# EncoderPCB_V2_lower.net
KiCad netlist of a schematic drawn in EAGLE
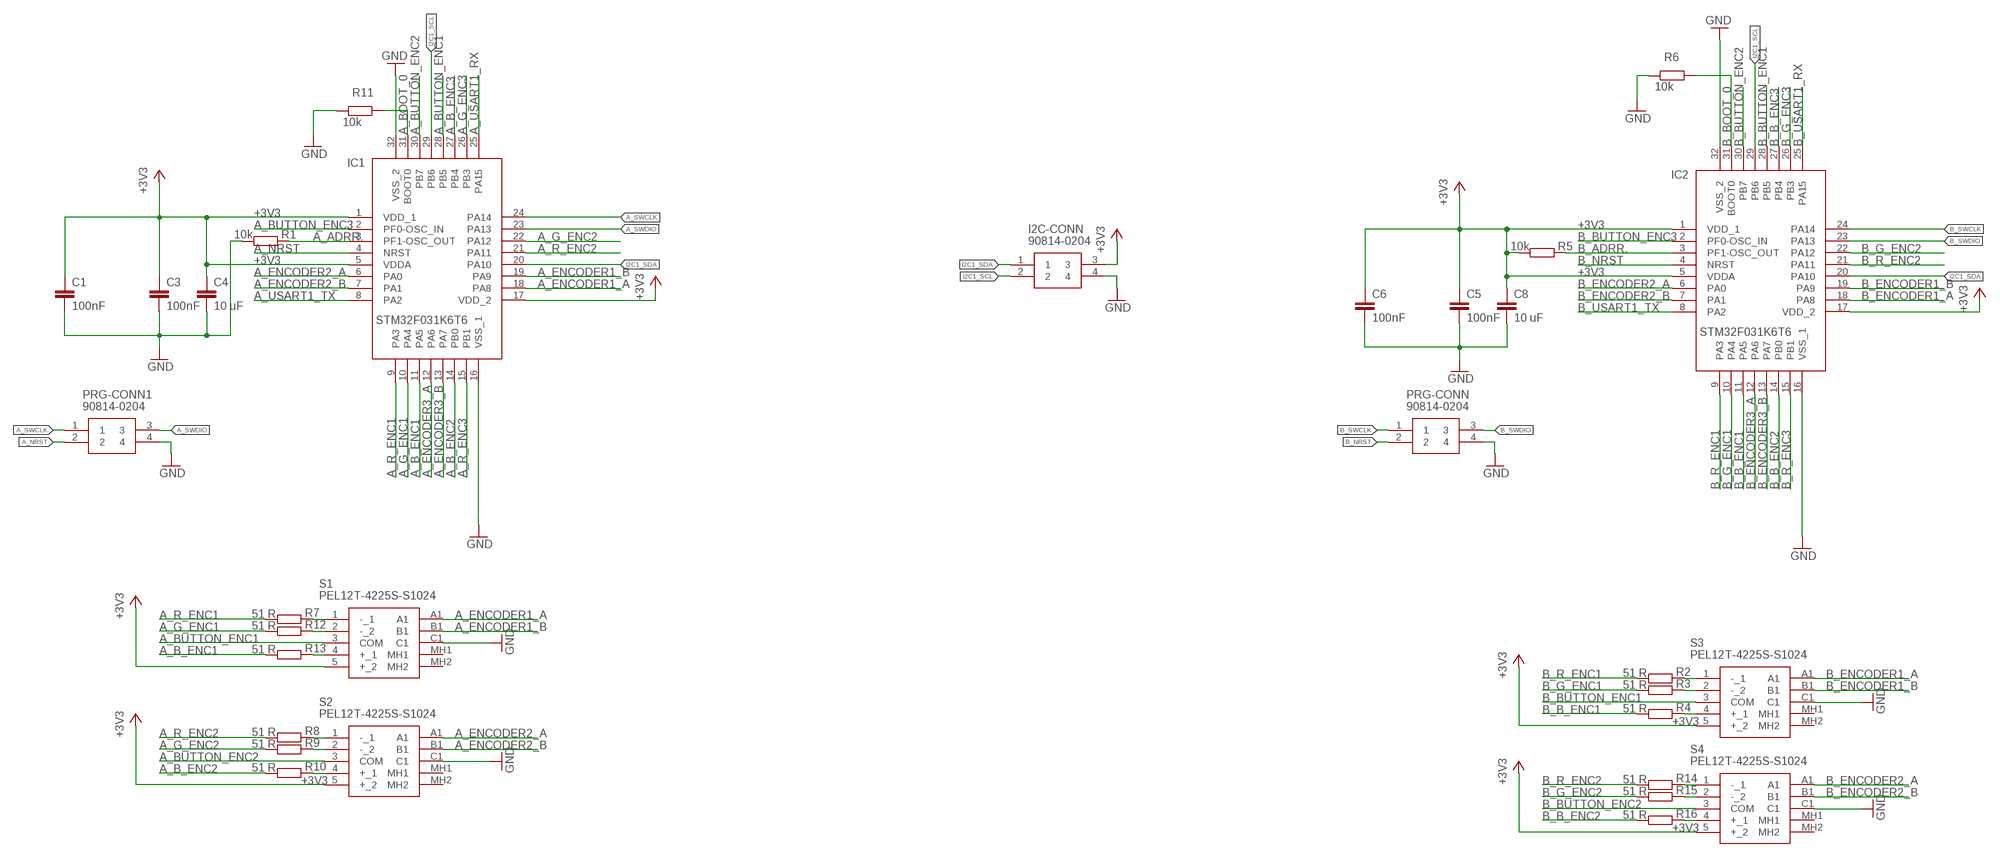
[diagram p0: schematic, sheet 1]

(export (version "E")
  (design (tool "Eeschema 10.0.6"))
  (components
    (comp (ref "C1")
      (value "100nF")
      (footprint "eagle-import:C0603")
      (libsource (lib "eagle-import") (part "CAPACITOR{dblquote}"))
    )
    (comp (ref "C3")
      (value "100nF")
      (footprint "eagle-import:C0603")
      (libsource (lib "eagle-import") (part "CAPACITOR{dblquote}"))
    )
    (comp (ref "C4")
      (value "10 uF")
      (footprint "eagle-import:C1206")
      (libsource (lib "eagle-import") (part "CAPACITOR_1206"))
    )
    (comp (ref "C5")
      (value "100nF")
      (footprint "eagle-import:C0603")
      (libsource (lib "eagle-import") (part "CAPACITOR{dblquote}"))
    )
    (comp (ref "C6")
      (value "100nF")
      (footprint "eagle-import:C0603")
      (libsource (lib "eagle-import") (part "CAPACITOR{dblquote}"))
    )
    (comp (ref "C8")
      (value "10 uF")
      (footprint "eagle-import:C1206")
      (libsource (lib "eagle-import") (part "CAPACITOR_1206"))
    )
    (comp (ref "I2C-CONN")
      (value "90814-0204")
      (footprint "eagle-import:MOLEX_90814-0204")
      (fields (field (name "MOUSER_PART_NUMBER") "538-90814-0204"))
      (libsource (lib "eagle-import") (part "90814-0204"))
    )
    (comp (ref "IC1")
      (value "STM32F031K6T6")
      (footprint "eagle-import:QFP80P900X900X160-32N")
      (fields (field (name "MOUSER_PART_NUMBER") "511-STM32F031K6T6"))
      (libsource (lib "eagle-import") (part "STM32F031K6T6"))
    )
    (comp (ref "IC2")
      (value "STM32F031K6T6")
      (footprint "eagle-import:QFP80P900X900X160-32N")
      (fields (field (name "MOUSER_PART_NUMBER") "511-STM32F031K6T6"))
      (libsource (lib "eagle-import") (part "STM32F031K6T6"))
    )
    (comp (ref "PRG-CONN")
      (value "90814-0204")
      (footprint "eagle-import:MOLEX_90814-0204")
      (fields (field (name "MOUSER_PART_NUMBER") "538-90814-0204"))
      (libsource (lib "eagle-import") (part "90814-0204"))
    )
    (comp (ref "PRG-CONN1")
      (value "90814-0204")
      (footprint "eagle-import:MOLEX_90814-0204")
      (fields (field (name "MOUSER_PART_NUMBER") "538-90814-0204"))
      (libsource (lib "eagle-import") (part "90814-0204"))
    )
    (comp (ref "R1")
      (value "10k")
      (footprint "eagle-import:R0603")
      (libsource (lib "eagle-import") (part "RESISTOR_0603"))
    )
    (comp (ref "R2")
      (value "51 R")
      (footprint "eagle-import:R0603")
      (libsource (lib "eagle-import") (part "RESISTOR_0603"))
    )
    (comp (ref "R3")
      (value "51 R")
      (footprint "eagle-import:R0603")
      (libsource (lib "eagle-import") (part "RESISTOR_0603"))
    )
    (comp (ref "R4")
      (value "51 R")
      (footprint "eagle-import:R0603")
      (libsource (lib "eagle-import") (part "RESISTOR_0603"))
    )
    (comp (ref "R5")
      (value "10k")
      (footprint "eagle-import:R0603")
      (libsource (lib "eagle-import") (part "RESISTOR_0603"))
    )
    (comp (ref "R6")
      (value "10k")
      (footprint "eagle-import:R0603")
      (libsource (lib "eagle-import") (part "RESISTOR_0603"))
    )
    (comp (ref "R7")
      (value "51 R")
      (footprint "eagle-import:R0603")
      (libsource (lib "eagle-import") (part "RESISTOR_0603"))
    )
    (comp (ref "R8")
      (value "51 R")
      (footprint "eagle-import:R0603")
      (libsource (lib "eagle-import") (part "RESISTOR_0603"))
    )
    (comp (ref "R9")
      (value "51 R")
      (footprint "eagle-import:R0603")
      (libsource (lib "eagle-import") (part "RESISTOR_0603"))
    )
    (comp (ref "R10")
      (value "51 R")
      (footprint "eagle-import:R0603")
      (libsource (lib "eagle-import") (part "RESISTOR_0603"))
    )
    (comp (ref "R11")
      (value "10k")
      (footprint "eagle-import:R0603")
      (libsource (lib "eagle-import") (part "RESISTOR_0603"))
    )
    (comp (ref "R12")
      (value "51 R")
      (footprint "eagle-import:R0603")
      (libsource (lib "eagle-import") (part "RESISTOR_0603"))
    )
    (comp (ref "R13")
      (value "51 R")
      (footprint "eagle-import:R0603")
      (libsource (lib "eagle-import") (part "RESISTOR_0603"))
    )
    (comp (ref "R14")
      (value "51 R")
      (footprint "eagle-import:R0603")
      (libsource (lib "eagle-import") (part "RESISTOR_0603"))
    )
    (comp (ref "R15")
      (value "51 R")
      (footprint "eagle-import:R0603")
      (libsource (lib "eagle-import") (part "RESISTOR_0603"))
    )
    (comp (ref "R16")
      (value "51 R")
      (footprint "eagle-import:R0603")
      (libsource (lib "eagle-import") (part "RESISTOR_0603"))
    )
    (comp (ref "S1")
      (value "PEL12T-4225S-S1024")
      (footprint "eagle-import:PEL12T4225SS1024")
      (fields (field (name "MOUSER_PART_NUMBER") "652-PEL12T4225SS1024"))
      (libsource (lib "eagle-import") (part "PEL12T-4225S-S1024"))
    )
    (comp (ref "S2")
      (value "PEL12T-4225S-S1024")
      (footprint "eagle-import:PEL12T4225SS1024")
      (fields (field (name "MOUSER_PART_NUMBER") "652-PEL12T4225SS1024"))
      (libsource (lib "eagle-import") (part "PEL12T-4225S-S1024"))
    )
    (comp (ref "S3")
      (value "PEL12T-4225S-S1024")
      (footprint "eagle-import:PEL12T4225SS1024")
      (fields (field (name "MOUSER_PART_NUMBER") "652-PEL12T4225SS1024"))
      (libsource (lib "eagle-import") (part "PEL12T-4225S-S1024"))
    )
    (comp (ref "S4")
      (value "PEL12T-4225S-S1024")
      (footprint "eagle-import:PEL12T4225SS1024")
      (fields (field (name "MOUSER_PART_NUMBER") "652-PEL12T4225SS1024"))
      (libsource (lib "eagle-import") (part "PEL12T-4225S-S1024"))
    )
  )
  (nets
    (net (code "1") (name "+3V3") (class "Default")
      (node (ref "C1") (pin "1") (pinfunction "1_1") (pintype "passive"))
      (node (ref "C3") (pin "1") (pinfunction "1_1") (pintype "passive"))
      (node (ref "C4") (pin "1") (pinfunction "1_1") (pintype "passive"))
      (node (ref "C5") (pin "1") (pinfunction "1_1") (pintype "passive"))
      (node (ref "C6") (pin "1") (pinfunction "1_1") (pintype "passive"))
      (node (ref "C8") (pin "1") (pinfunction "1_1") (pintype "passive"))
      (node (ref "I2C-CONN") (pin "3") (pinfunction "3_3") (pintype "bidirectional"))
      (node (ref "IC1") (pin "1") (pinfunction "VDD_1_1") (pintype "bidirectional"))
      (node (ref "IC1") (pin "17") (pinfunction "VDD_2_17") (pintype "bidirectional"))
      (node (ref "IC1") (pin "5") (pinfunction "VDDA_5") (pintype "bidirectional"))
      (node (ref "IC2") (pin "1") (pinfunction "VDD_1_1") (pintype "bidirectional"))
      (node (ref "IC2") (pin "17") (pinfunction "VDD_2_17") (pintype "bidirectional"))
      (node (ref "IC2") (pin "5") (pinfunction "VDDA_5") (pintype "bidirectional"))
      (node (ref "R5") (pin "1") (pinfunction "1_1") (pintype "passive"))
      (node (ref "S1") (pin "5") (pinfunction "+_2_5") (pintype "bidirectional"))
      (node (ref "S2") (pin "5") (pinfunction "+_2_5") (pintype "bidirectional"))
      (node (ref "S3") (pin "5") (pinfunction "+_2_5") (pintype "bidirectional"))
      (node (ref "S4") (pin "5") (pinfunction "+_2_5") (pintype "bidirectional"))
    )
    (net (code "2") (name "/A_ADRR.") (class "Default")
      (node (ref "IC1") (pin "3") (pinfunction "PF1-OSC_OUT_3") (pintype "bidirectional"))
      (node (ref "R1") (pin "2") (pinfunction "2_2") (pintype "passive"))
    )
    (net (code "3") (name "/A_BOOT_0") (class "Default")
      (node (ref "IC1") (pin "31") (pinfunction "BOOT0_31") (pintype "bidirectional"))
      (node (ref "R11") (pin "2") (pinfunction "2_2") (pintype "passive"))
    )
    (net (code "4") (name "/A_BUTTON_ENC1") (class "Default")
      (node (ref "IC1") (pin "28") (pinfunction "PB5_28") (pintype "bidirectional"))
      (node (ref "S1") (pin "3") (pinfunction "COM_3") (pintype "bidirectional"))
    )
    (net (code "5") (name "/A_BUTTON_ENC2") (class "Default")
      (node (ref "IC1") (pin "30") (pinfunction "PB7_30") (pintype "bidirectional"))
      (node (ref "S2") (pin "3") (pinfunction "COM_3") (pintype "bidirectional"))
    )
    (net (code "6") (name "/A_BUTTON_ENC3") (class "Default")
      (node (ref "IC1") (pin "2") (pinfunction "PF0-OSC_IN_2") (pintype "bidirectional"))
    )
    (net (code "7") (name "/A_B_ENC1") (class "Default")
      (node (ref "IC1") (pin "11") (pinfunction "PA5_11") (pintype "bidirectional"))
      (node (ref "R13") (pin "1") (pinfunction "1_1") (pintype "passive"))
    )
    (net (code "8") (name "/A_B_ENC2") (class "Default")
      (node (ref "IC1") (pin "14") (pinfunction "PB0_14") (pintype "bidirectional"))
      (node (ref "R10") (pin "1") (pinfunction "1_1") (pintype "passive"))
    )
    (net (code "9") (name "/A_B_ENC3") (class "Default")
      (node (ref "IC1") (pin "27") (pinfunction "PB4_27") (pintype "bidirectional"))
    )
    (net (code "10") (name "/A_ENCODER1_A") (class "Default")
      (node (ref "IC1") (pin "18") (pinfunction "PA8_18") (pintype "bidirectional"))
      (node (ref "S1") (pin "A1") (pinfunction "A1_A1") (pintype "bidirectional"))
    )
    (net (code "11") (name "/A_ENCODER1_B") (class "Default")
      (node (ref "IC1") (pin "19") (pinfunction "PA9_19") (pintype "bidirectional"))
      (node (ref "S1") (pin "B1") (pinfunction "B1_B1") (pintype "bidirectional"))
    )
    (net (code "12") (name "/A_ENCODER2_A") (class "Default")
      (node (ref "IC1") (pin "6") (pinfunction "PA0_6") (pintype "bidirectional"))
      (node (ref "S2") (pin "A1") (pinfunction "A1_A1") (pintype "bidirectional"))
    )
    (net (code "13") (name "/A_ENCODER2_B") (class "Default")
      (node (ref "IC1") (pin "7") (pinfunction "PA1_7") (pintype "bidirectional"))
      (node (ref "S2") (pin "B1") (pinfunction "B1_B1") (pintype "bidirectional"))
    )
    (net (code "14") (name "/A_ENCODER3_A") (class "Default")
      (node (ref "IC1") (pin "12") (pinfunction "PA6_12") (pintype "bidirectional"))
    )
    (net (code "15") (name "/A_ENCODER3_B") (class "Default")
      (node (ref "IC1") (pin "13") (pinfunction "PA7_13") (pintype "bidirectional"))
    )
    (net (code "16") (name "/A_G_ENC1") (class "Default")
      (node (ref "IC1") (pin "10") (pinfunction "PA4_10") (pintype "bidirectional"))
      (node (ref "R12") (pin "1") (pinfunction "1_1") (pintype "passive"))
    )
    (net (code "17") (name "/A_G_ENC2") (class "Default")
      (node (ref "IC1") (pin "22") (pinfunction "PA12_22") (pintype "bidirectional"))
      (node (ref "R9") (pin "1") (pinfunction "1_1") (pintype "passive"))
    )
    (net (code "18") (name "/A_G_ENC3") (class "Default")
      (node (ref "IC1") (pin "26") (pinfunction "PB3_26") (pintype "bidirectional"))
    )
    (net (code "19") (name "/A_R_ENC1") (class "Default")
      (node (ref "IC1") (pin "9") (pinfunction "PA3_9") (pintype "bidirectional"))
      (node (ref "R7") (pin "1") (pinfunction "1_1") (pintype "passive"))
    )
    (net (code "20") (name "/A_R_ENC2") (class "Default")
      (node (ref "IC1") (pin "21") (pinfunction "PA11_21") (pintype "bidirectional"))
      (node (ref "R8") (pin "1") (pinfunction "1_1") (pintype "passive"))
    )
    (net (code "21") (name "/A_R_ENC3") (class "Default")
      (node (ref "IC1") (pin "15") (pinfunction "PB1_15") (pintype "bidirectional"))
    )
    (net (code "22") (name "/A_USART1_RX") (class "Default")
      (node (ref "IC1") (pin "25") (pinfunction "PA15_25") (pintype "bidirectional"))
    )
    (net (code "23") (name "/A_USART1_TX") (class "Default")
      (node (ref "IC1") (pin "8") (pinfunction "PA2_8") (pintype "bidirectional"))
    )
    (net (code "24") (name "/B_ADRR.") (class "Default")
      (node (ref "IC2") (pin "3") (pinfunction "PF1-OSC_OUT_3") (pintype "bidirectional"))
      (node (ref "R5") (pin "2") (pinfunction "2_2") (pintype "passive"))
    )
    (net (code "25") (name "/B_BOOT_0") (class "Default")
      (node (ref "IC2") (pin "31") (pinfunction "BOOT0_31") (pintype "bidirectional"))
      (node (ref "R6") (pin "2") (pinfunction "2_2") (pintype "passive"))
    )
    (net (code "26") (name "/B_BUTTON_ENC1") (class "Default")
      (node (ref "IC2") (pin "28") (pinfunction "PB5_28") (pintype "bidirectional"))
      (node (ref "S3") (pin "3") (pinfunction "COM_3") (pintype "bidirectional"))
    )
    (net (code "27") (name "/B_BUTTON_ENC2") (class "Default")
      (node (ref "IC2") (pin "30") (pinfunction "PB7_30") (pintype "bidirectional"))
      (node (ref "S4") (pin "3") (pinfunction "COM_3") (pintype "bidirectional"))
    )
    (net (code "28") (name "/B_BUTTON_ENC3") (class "Default")
      (node (ref "IC2") (pin "2") (pinfunction "PF0-OSC_IN_2") (pintype "bidirectional"))
    )
    (net (code "29") (name "/B_B_ENC1") (class "Default")
      (node (ref "IC2") (pin "11") (pinfunction "PA5_11") (pintype "bidirectional"))
      (node (ref "R4") (pin "1") (pinfunction "1_1") (pintype "passive"))
    )
    (net (code "30") (name "/B_B_ENC2") (class "Default")
      (node (ref "IC2") (pin "14") (pinfunction "PB0_14") (pintype "bidirectional"))
      (node (ref "R16") (pin "1") (pinfunction "1_1") (pintype "passive"))
    )
    (net (code "31") (name "/B_B_ENC3") (class "Default")
      (node (ref "IC2") (pin "27") (pinfunction "PB4_27") (pintype "bidirectional"))
    )
    (net (code "32") (name "/B_ENCODER1_A") (class "Default")
      (node (ref "IC2") (pin "18") (pinfunction "PA8_18") (pintype "bidirectional"))
      (node (ref "S3") (pin "A1") (pinfunction "A1_A1") (pintype "bidirectional"))
    )
    (net (code "33") (name "/B_ENCODER1_B") (class "Default")
      (node (ref "IC2") (pin "19") (pinfunction "PA9_19") (pintype "bidirectional"))
      (node (ref "S3") (pin "B1") (pinfunction "B1_B1") (pintype "bidirectional"))
    )
    (net (code "34") (name "/B_ENCODER2_A") (class "Default")
      (node (ref "IC2") (pin "6") (pinfunction "PA0_6") (pintype "bidirectional"))
      (node (ref "S4") (pin "A1") (pinfunction "A1_A1") (pintype "bidirectional"))
    )
    (net (code "35") (name "/B_ENCODER2_B") (class "Default")
      (node (ref "IC2") (pin "7") (pinfunction "PA1_7") (pintype "bidirectional"))
      (node (ref "S4") (pin "B1") (pinfunction "B1_B1") (pintype "bidirectional"))
    )
    (net (code "36") (name "/B_ENCODER3_A") (class "Default")
      (node (ref "IC2") (pin "12") (pinfunction "PA6_12") (pintype "bidirectional"))
    )
    (net (code "37") (name "/B_ENCODER3_B") (class "Default")
      (node (ref "IC2") (pin "13") (pinfunction "PA7_13") (pintype "bidirectional"))
    )
    (net (code "38") (name "/B_G_ENC1") (class "Default")
      (node (ref "IC2") (pin "10") (pinfunction "PA4_10") (pintype "bidirectional"))
      (node (ref "R3") (pin "1") (pinfunction "1_1") (pintype "passive"))
    )
    (net (code "39") (name "/B_G_ENC2") (class "Default")
      (node (ref "IC2") (pin "22") (pinfunction "PA12_22") (pintype "bidirectional"))
      (node (ref "R15") (pin "1") (pinfunction "1_1") (pintype "passive"))
    )
    (net (code "40") (name "/B_G_ENC3") (class "Default")
      (node (ref "IC2") (pin "26") (pinfunction "PB3_26") (pintype "bidirectional"))
    )
    (net (code "41") (name "/B_R_ENC1") (class "Default")
      (node (ref "IC2") (pin "9") (pinfunction "PA3_9") (pintype "bidirectional"))
      (node (ref "R2") (pin "1") (pinfunction "1_1") (pintype "passive"))
    )
    (net (code "42") (name "/B_R_ENC2") (class "Default")
      (node (ref "IC2") (pin "21") (pinfunction "PA11_21") (pintype "bidirectional"))
      (node (ref "R14") (pin "1") (pinfunction "1_1") (pintype "passive"))
    )
    (net (code "43") (name "/B_R_ENC3") (class "Default")
      (node (ref "IC2") (pin "15") (pinfunction "PB1_15") (pintype "bidirectional"))
    )
    (net (code "44") (name "/B_USART1_RX") (class "Default")
      (node (ref "IC2") (pin "25") (pinfunction "PA15_25") (pintype "bidirectional"))
    )
    (net (code "45") (name "/B_USART1_TX") (class "Default")
      (node (ref "IC2") (pin "8") (pinfunction "PA2_8") (pintype "bidirectional"))
    )
    (net (code "46") (name "A_NRST") (class "Default")
      (node (ref "IC1") (pin "4") (pinfunction "NRST_4") (pintype "bidirectional"))
      (node (ref "PRG-CONN1") (pin "2") (pinfunction "2_2") (pintype "bidirectional"))
    )
    (net (code "47") (name "A_SWCLK") (class "Default")
      (node (ref "IC1") (pin "24") (pinfunction "PA14_24") (pintype "bidirectional"))
      (node (ref "PRG-CONN1") (pin "1") (pinfunction "1_1") (pintype "bidirectional"))
    )
    (net (code "48") (name "A_SWDIO") (class "Default")
      (node (ref "IC1") (pin "23") (pinfunction "PA13_23") (pintype "bidirectional"))
      (node (ref "PRG-CONN1") (pin "3") (pinfunction "3_3") (pintype "bidirectional"))
    )
    (net (code "49") (name "B_NRST") (class "Default")
      (node (ref "IC2") (pin "4") (pinfunction "NRST_4") (pintype "bidirectional"))
      (node (ref "PRG-CONN") (pin "2") (pinfunction "2_2") (pintype "bidirectional"))
    )
    (net (code "50") (name "B_SWCLK") (class "Default")
      (node (ref "IC2") (pin "24") (pinfunction "PA14_24") (pintype "bidirectional"))
      (node (ref "PRG-CONN") (pin "1") (pinfunction "1_1") (pintype "bidirectional"))
    )
    (net (code "51") (name "B_SWDIO") (class "Default")
      (node (ref "IC2") (pin "23") (pinfunction "PA13_23") (pintype "bidirectional"))
      (node (ref "PRG-CONN") (pin "3") (pinfunction "3_3") (pintype "bidirectional"))
    )
    (net (code "52") (name "GND") (class "Default")
      (node (ref "C1") (pin "2") (pinfunction "2_2") (pintype "passive"))
      (node (ref "C3") (pin "2") (pinfunction "2_2") (pintype "passive"))
      (node (ref "C4") (pin "2") (pinfunction "2_2") (pintype "passive"))
      (node (ref "C5") (pin "2") (pinfunction "2_2") (pintype "passive"))
      (node (ref "C6") (pin "2") (pinfunction "2_2") (pintype "passive"))
      (node (ref "C8") (pin "2") (pinfunction "2_2") (pintype "passive"))
      (node (ref "I2C-CONN") (pin "4") (pinfunction "4_4") (pintype "bidirectional"))
      (node (ref "IC1") (pin "16") (pinfunction "VSS_1_16") (pintype "bidirectional"))
      (node (ref "IC1") (pin "32") (pinfunction "VSS_2_32") (pintype "bidirectional"))
      (node (ref "IC2") (pin "16") (pinfunction "VSS_1_16") (pintype "bidirectional"))
      (node (ref "IC2") (pin "32") (pinfunction "VSS_2_32") (pintype "bidirectional"))
      (node (ref "PRG-CONN") (pin "4") (pinfunction "4_4") (pintype "bidirectional"))
      (node (ref "PRG-CONN1") (pin "4") (pinfunction "4_4") (pintype "bidirectional"))
      (node (ref "R1") (pin "1") (pinfunction "1_1") (pintype "passive"))
      (node (ref "R11") (pin "1") (pinfunction "1_1") (pintype "passive"))
      (node (ref "R6") (pin "1") (pinfunction "1_1") (pintype "passive"))
      (node (ref "S1") (pin "C1") (pinfunction "C1_C1") (pintype "bidirectional"))
      (node (ref "S2") (pin "C1") (pinfunction "C1_C1") (pintype "bidirectional"))
      (node (ref "S3") (pin "C1") (pinfunction "C1_C1") (pintype "bidirectional"))
      (node (ref "S4") (pin "C1") (pinfunction "C1_C1") (pintype "bidirectional"))
    )
    (net (code "53") (name "I2C1_SCL") (class "Default")
      (node (ref "I2C-CONN") (pin "2") (pinfunction "2_2") (pintype "bidirectional"))
      (node (ref "IC1") (pin "29") (pinfunction "PB6_29") (pintype "bidirectional"))
      (node (ref "IC2") (pin "29") (pinfunction "PB6_29") (pintype "bidirectional"))
    )
    (net (code "54") (name "I2C1_SDA") (class "Default")
      (node (ref "I2C-CONN") (pin "1") (pinfunction "1_1") (pintype "bidirectional"))
      (node (ref "IC1") (pin "20") (pinfunction "PA10_20") (pintype "bidirectional"))
      (node (ref "IC2") (pin "20") (pinfunction "PA10_20") (pintype "bidirectional"))
    )
    (net (code "55") (name "Net-(S1-+_1)") (class "Default")
      (node (ref "R13") (pin "2") (pinfunction "2_2") (pintype "passive"))
      (node (ref "S1") (pin "4") (pinfunction "+_1_4") (pintype "bidirectional"))
    )
    (net (code "56") (name "Net-(S1--_1)") (class "Default")
      (node (ref "R7") (pin "2") (pinfunction "2_2") (pintype "passive"))
      (node (ref "S1") (pin "1") (pinfunction "-_1_1") (pintype "bidirectional"))
    )
    (net (code "57") (name "Net-(S1--_2)") (class "Default")
      (node (ref "R12") (pin "2") (pinfunction "2_2") (pintype "passive"))
      (node (ref "S1") (pin "2") (pinfunction "-_2_2") (pintype "bidirectional"))
    )
    (net (code "58") (name "Net-(S2-+_1)") (class "Default")
      (node (ref "R10") (pin "2") (pinfunction "2_2") (pintype "passive"))
      (node (ref "S2") (pin "4") (pinfunction "+_1_4") (pintype "bidirectional"))
    )
    (net (code "59") (name "Net-(S2--_1)") (class "Default")
      (node (ref "R8") (pin "2") (pinfunction "2_2") (pintype "passive"))
      (node (ref "S2") (pin "1") (pinfunction "-_1_1") (pintype "bidirectional"))
    )
    (net (code "60") (name "Net-(S2--_2)") (class "Default")
      (node (ref "R9") (pin "2") (pinfunction "2_2") (pintype "passive"))
      (node (ref "S2") (pin "2") (pinfunction "-_2_2") (pintype "bidirectional"))
    )
    (net (code "61") (name "Net-(S3-+_1)") (class "Default")
      (node (ref "R4") (pin "2") (pinfunction "2_2") (pintype "passive"))
      (node (ref "S3") (pin "4") (pinfunction "+_1_4") (pintype "bidirectional"))
    )
    (net (code "62") (name "Net-(S3--_1)") (class "Default")
      (node (ref "R2") (pin "2") (pinfunction "2_2") (pintype "passive"))
      (node (ref "S3") (pin "1") (pinfunction "-_1_1") (pintype "bidirectional"))
    )
    (net (code "63") (name "Net-(S3--_2)") (class "Default")
      (node (ref "R3") (pin "2") (pinfunction "2_2") (pintype "passive"))
      (node (ref "S3") (pin "2") (pinfunction "-_2_2") (pintype "bidirectional"))
    )
    (net (code "64") (name "Net-(S4-+_1)") (class "Default")
      (node (ref "R16") (pin "2") (pinfunction "2_2") (pintype "passive"))
      (node (ref "S4") (pin "4") (pinfunction "+_1_4") (pintype "bidirectional"))
    )
    (net (code "65") (name "Net-(S4--_1)") (class "Default")
      (node (ref "R14") (pin "2") (pinfunction "2_2") (pintype "passive"))
      (node (ref "S4") (pin "1") (pinfunction "-_1_1") (pintype "bidirectional"))
    )
    (net (code "66") (name "Net-(S4--_2)") (class "Default")
      (node (ref "R15") (pin "2") (pinfunction "2_2") (pintype "passive"))
      (node (ref "S4") (pin "2") (pinfunction "-_2_2") (pintype "bidirectional"))
    )
    (net (code "67") (name "unconnected-(S1-PadMH1)") (class "Default")
      (node (ref "S1") (pin "MH1") (pinfunction "MH1_MH1") (pintype "bidirectional"))
    )
    (net (code "68") (name "unconnected-(S1-PadMH2)") (class "Default")
      (node (ref "S1") (pin "MH2") (pinfunction "MH2_MH2") (pintype "bidirectional"))
    )
    (net (code "69") (name "unconnected-(S2-PadMH1)") (class "Default")
      (node (ref "S2") (pin "MH1") (pinfunction "MH1_MH1") (pintype "bidirectional"))
    )
    (net (code "70") (name "unconnected-(S2-PadMH2)") (class "Default")
      (node (ref "S2") (pin "MH2") (pinfunction "MH2_MH2") (pintype "bidirectional"))
    )
    (net (code "71") (name "unconnected-(S3-PadMH1)") (class "Default")
      (node (ref "S3") (pin "MH1") (pinfunction "MH1_MH1") (pintype "bidirectional"))
    )
    (net (code "72") (name "unconnected-(S3-PadMH2)") (class "Default")
      (node (ref "S3") (pin "MH2") (pinfunction "MH2_MH2") (pintype "bidirectional"))
    )
    (net (code "73") (name "unconnected-(S4-PadMH1)") (class "Default")
      (node (ref "S4") (pin "MH1") (pinfunction "MH1_MH1") (pintype "bidirectional"))
    )
    (net (code "74") (name "unconnected-(S4-PadMH2)") (class "Default")
      (node (ref "S4") (pin "MH2") (pinfunction "MH2_MH2") (pintype "bidirectional"))
    )
  )
)
